# Input_v1_0.net
KiCad netlist of a schematic drawn in EAGLE
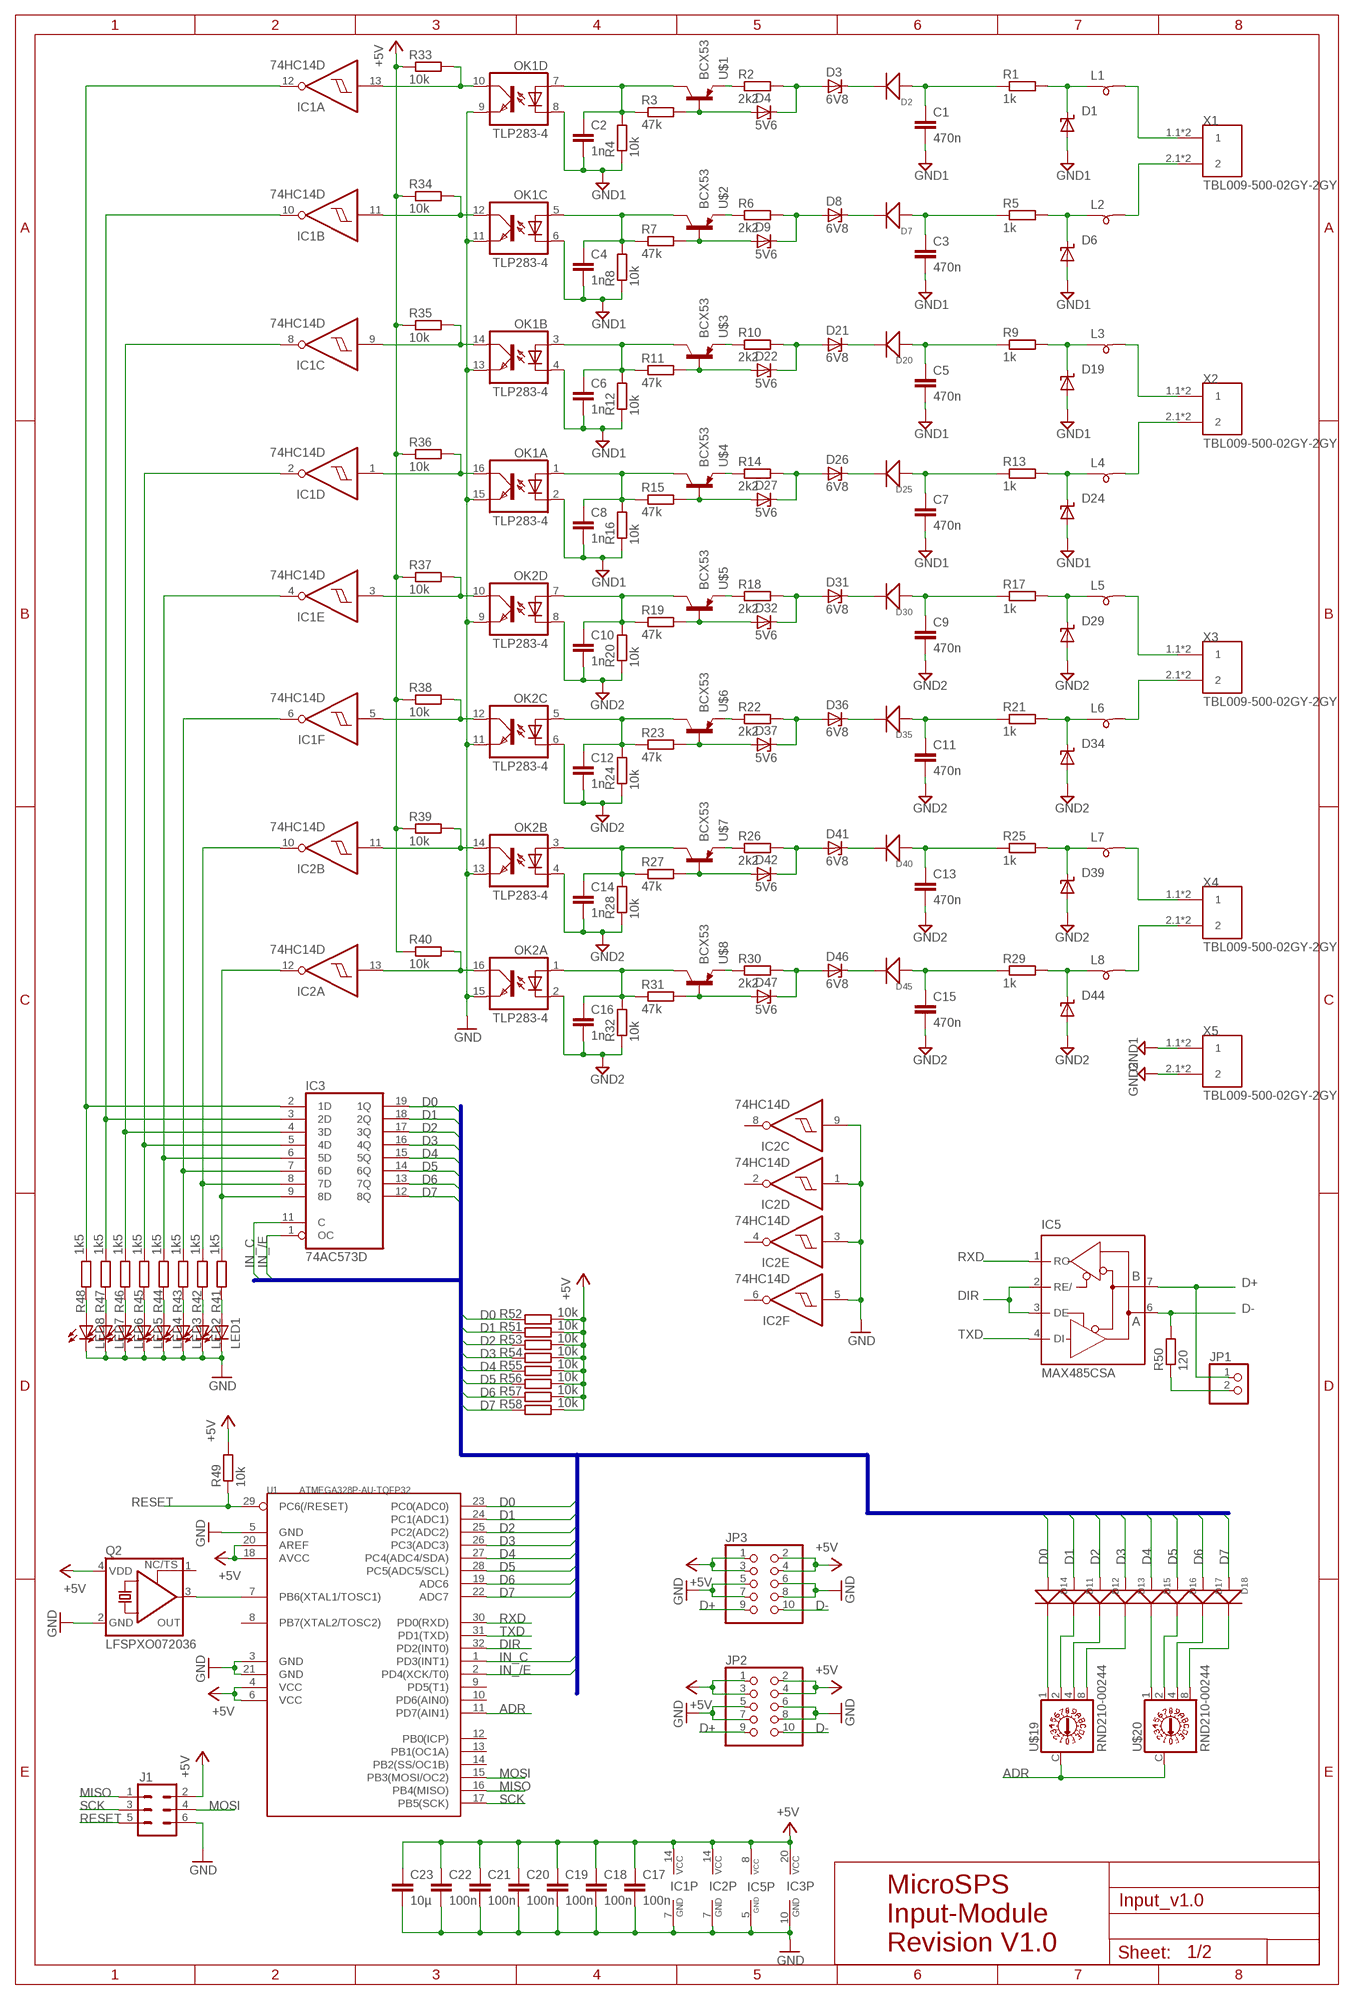
[diagram p0: schematic, sheet 1]

(export (version "E")
  (design (tool "Eeschema 10.0.6"))
  (components
    (comp (ref "C1")
      (value "470n")
      (footprint "eagle-import:C0805")
      (libsource (lib "eagle-import") (part "C-EUC0805"))
    )
    (comp (ref "C2")
      (value "1n")
      (footprint "eagle-import:C0805")
      (libsource (lib "eagle-import") (part "C-EUC0805"))
    )
    (comp (ref "C3")
      (value "470n")
      (footprint "eagle-import:C0805")
      (libsource (lib "eagle-import") (part "C-EUC0805"))
    )
    (comp (ref "C4")
      (value "1n")
      (footprint "eagle-import:C0805")
      (libsource (lib "eagle-import") (part "C-EUC0805"))
    )
    (comp (ref "C5")
      (value "470n")
      (footprint "eagle-import:C0805")
      (libsource (lib "eagle-import") (part "C-EUC0805"))
    )
    (comp (ref "C6")
      (value "1n")
      (footprint "eagle-import:C0805")
      (libsource (lib "eagle-import") (part "C-EUC0805"))
    )
    (comp (ref "C7")
      (value "470n")
      (footprint "eagle-import:C0805")
      (libsource (lib "eagle-import") (part "C-EUC0805"))
    )
    (comp (ref "C8")
      (value "1n")
      (footprint "eagle-import:C0805")
      (libsource (lib "eagle-import") (part "C-EUC0805"))
    )
    (comp (ref "C9")
      (value "470n")
      (footprint "eagle-import:C0805")
      (libsource (lib "eagle-import") (part "C-EUC0805"))
    )
    (comp (ref "C10")
      (value "1n")
      (footprint "eagle-import:C0805")
      (libsource (lib "eagle-import") (part "C-EUC0805"))
    )
    (comp (ref "C11")
      (value "470n")
      (footprint "eagle-import:C0805")
      (libsource (lib "eagle-import") (part "C-EUC0805"))
    )
    (comp (ref "C12")
      (value "1n")
      (footprint "eagle-import:C0805")
      (libsource (lib "eagle-import") (part "C-EUC0805"))
    )
    (comp (ref "C13")
      (value "470n")
      (footprint "eagle-import:C0805")
      (libsource (lib "eagle-import") (part "C-EUC0805"))
    )
    (comp (ref "C14")
      (value "1n")
      (footprint "eagle-import:C0805")
      (libsource (lib "eagle-import") (part "C-EUC0805"))
    )
    (comp (ref "C15")
      (value "470n")
      (footprint "eagle-import:C0805")
      (libsource (lib "eagle-import") (part "C-EUC0805"))
    )
    (comp (ref "C16")
      (value "1n")
      (footprint "eagle-import:C0805")
      (libsource (lib "eagle-import") (part "C-EUC0805"))
    )
    (comp (ref "C17")
      (value "100n")
      (footprint "eagle-import:C0805")
      (libsource (lib "eagle-import") (part "C-EUC0805"))
    )
    (comp (ref "C18")
      (value "100n")
      (footprint "eagle-import:C0805")
      (libsource (lib "eagle-import") (part "C-EUC0805"))
    )
    (comp (ref "C19")
      (value "100n")
      (footprint "eagle-import:C0805")
      (libsource (lib "eagle-import") (part "C-EUC0805"))
    )
    (comp (ref "C20")
      (value "100n")
      (footprint "eagle-import:C0805")
      (libsource (lib "eagle-import") (part "C-EUC0805"))
    )
    (comp (ref "C21")
      (value "100n")
      (footprint "eagle-import:C0805")
      (libsource (lib "eagle-import") (part "C-EUC0805"))
    )
    (comp (ref "C22")
      (value "100n")
      (footprint "eagle-import:C0805")
      (libsource (lib "eagle-import") (part "C-EUC0805"))
    )
    (comp (ref "C23")
      (value "10µ")
      (footprint "eagle-import:C0805")
      (libsource (lib "eagle-import") (part "C-EUC0805"))
    )
    (comp (ref "D1")
      (value "SUPPRESSOR-SMBJ")
      (footprint "eagle-import:SMBJ")
      (libsource (lib "eagle-import") (part "SUPPRESSOR-SMBJ"))
    )
    (comp (ref "D2")
      (value "DIODE'1N4148-SMD'")
      (footprint "eagle-import:LL-34")
      (libsource (lib "eagle-import") (part "DIODE'1N4148-SMD'"))
    )
    (comp (ref "D3")
      (value "6V8")
      (footprint "eagle-import:SOD80C")
      (libsource (lib "eagle-import") (part "ZENER-DIODESOD80C"))
    )
    (comp (ref "D4")
      (value "5V6")
      (footprint "eagle-import:SOD80C")
      (libsource (lib "eagle-import") (part "ZENER-DIODESOD80C"))
    )
    (comp (ref "D6")
      (value "SUPPRESSOR-SMBJ")
      (footprint "eagle-import:SMBJ")
      (libsource (lib "eagle-import") (part "SUPPRESSOR-SMBJ"))
    )
    (comp (ref "D7")
      (value "DIODE'1N4148-SMD'")
      (footprint "eagle-import:LL-34")
      (libsource (lib "eagle-import") (part "DIODE'1N4148-SMD'"))
    )
    (comp (ref "D8")
      (value "6V8")
      (footprint "eagle-import:SOD80C")
      (libsource (lib "eagle-import") (part "ZENER-DIODESOD80C"))
    )
    (comp (ref "D9")
      (value "5V6")
      (footprint "eagle-import:SOD80C")
      (libsource (lib "eagle-import") (part "ZENER-DIODESOD80C"))
    )
    (comp (ref "D11")
      (value "DIODE'1N4148-SMD'")
      (footprint "eagle-import:LL-34")
      (libsource (lib "eagle-import") (part "DIODE'1N4148-SMD'"))
    )
    (comp (ref "D12")
      (value "DIODE'1N4148-SMD'")
      (footprint "eagle-import:LL-34")
      (libsource (lib "eagle-import") (part "DIODE'1N4148-SMD'"))
    )
    (comp (ref "D13")
      (value "DIODE'1N4148-SMD'")
      (footprint "eagle-import:LL-34")
      (libsource (lib "eagle-import") (part "DIODE'1N4148-SMD'"))
    )
    (comp (ref "D14")
      (value "DIODE'1N4148-SMD'")
      (footprint "eagle-import:LL-34")
      (libsource (lib "eagle-import") (part "DIODE'1N4148-SMD'"))
    )
    (comp (ref "D15")
      (value "DIODE'1N4148-SMD'")
      (footprint "eagle-import:LL-34")
      (libsource (lib "eagle-import") (part "DIODE'1N4148-SMD'"))
    )
    (comp (ref "D16")
      (value "DIODE'1N4148-SMD'")
      (footprint "eagle-import:LL-34")
      (libsource (lib "eagle-import") (part "DIODE'1N4148-SMD'"))
    )
    (comp (ref "D17")
      (value "DIODE'1N4148-SMD'")
      (footprint "eagle-import:LL-34")
      (libsource (lib "eagle-import") (part "DIODE'1N4148-SMD'"))
    )
    (comp (ref "D18")
      (value "DIODE'1N4148-SMD'")
      (footprint "eagle-import:LL-34")
      (libsource (lib "eagle-import") (part "DIODE'1N4148-SMD'"))
    )
    (comp (ref "D19")
      (value "SUPPRESSOR-SMBJ")
      (footprint "eagle-import:SMBJ")
      (libsource (lib "eagle-import") (part "SUPPRESSOR-SMBJ"))
    )
    (comp (ref "D20")
      (value "DIODE'1N4148-SMD'")
      (footprint "eagle-import:LL-34")
      (libsource (lib "eagle-import") (part "DIODE'1N4148-SMD'"))
    )
    (comp (ref "D21")
      (value "6V8")
      (footprint "eagle-import:SOD80C")
      (libsource (lib "eagle-import") (part "ZENER-DIODESOD80C"))
    )
    (comp (ref "D22")
      (value "5V6")
      (footprint "eagle-import:SOD80C")
      (libsource (lib "eagle-import") (part "ZENER-DIODESOD80C"))
    )
    (comp (ref "D24")
      (value "SUPPRESSOR-SMBJ")
      (footprint "eagle-import:SMBJ")
      (libsource (lib "eagle-import") (part "SUPPRESSOR-SMBJ"))
    )
    (comp (ref "D25")
      (value "DIODE'1N4148-SMD'")
      (footprint "eagle-import:LL-34")
      (libsource (lib "eagle-import") (part "DIODE'1N4148-SMD'"))
    )
    (comp (ref "D26")
      (value "6V8")
      (footprint "eagle-import:SOD80C")
      (libsource (lib "eagle-import") (part "ZENER-DIODESOD80C"))
    )
    (comp (ref "D27")
      (value "5V6")
      (footprint "eagle-import:SOD80C")
      (libsource (lib "eagle-import") (part "ZENER-DIODESOD80C"))
    )
    (comp (ref "D29")
      (value "SUPPRESSOR-SMBJ")
      (footprint "eagle-import:SMBJ")
      (libsource (lib "eagle-import") (part "SUPPRESSOR-SMBJ"))
    )
    (comp (ref "D30")
      (value "DIODE'1N4148-SMD'")
      (footprint "eagle-import:LL-34")
      (libsource (lib "eagle-import") (part "DIODE'1N4148-SMD'"))
    )
    (comp (ref "D31")
      (value "6V8")
      (footprint "eagle-import:SOD80C")
      (libsource (lib "eagle-import") (part "ZENER-DIODESOD80C"))
    )
    (comp (ref "D32")
      (value "5V6")
      (footprint "eagle-import:SOD80C")
      (libsource (lib "eagle-import") (part "ZENER-DIODESOD80C"))
    )
    (comp (ref "D34")
      (value "SUPPRESSOR-SMBJ")
      (footprint "eagle-import:SMBJ")
      (libsource (lib "eagle-import") (part "SUPPRESSOR-SMBJ"))
    )
    (comp (ref "D35")
      (value "DIODE'1N4148-SMD'")
      (footprint "eagle-import:LL-34")
      (libsource (lib "eagle-import") (part "DIODE'1N4148-SMD'"))
    )
    (comp (ref "D36")
      (value "6V8")
      (footprint "eagle-import:SOD80C")
      (libsource (lib "eagle-import") (part "ZENER-DIODESOD80C"))
    )
    (comp (ref "D37")
      (value "5V6")
      (footprint "eagle-import:SOD80C")
      (libsource (lib "eagle-import") (part "ZENER-DIODESOD80C"))
    )
    (comp (ref "D39")
      (value "SUPPRESSOR-SMBJ")
      (footprint "eagle-import:SMBJ")
      (libsource (lib "eagle-import") (part "SUPPRESSOR-SMBJ"))
    )
    (comp (ref "D40")
      (value "DIODE'1N4148-SMD'")
      (footprint "eagle-import:LL-34")
      (libsource (lib "eagle-import") (part "DIODE'1N4148-SMD'"))
    )
    (comp (ref "D41")
      (value "6V8")
      (footprint "eagle-import:SOD80C")
      (libsource (lib "eagle-import") (part "ZENER-DIODESOD80C"))
    )
    (comp (ref "D42")
      (value "5V6")
      (footprint "eagle-import:SOD80C")
      (libsource (lib "eagle-import") (part "ZENER-DIODESOD80C"))
    )
    (comp (ref "D44")
      (value "SUPPRESSOR-SMBJ")
      (footprint "eagle-import:SMBJ")
      (libsource (lib "eagle-import") (part "SUPPRESSOR-SMBJ"))
    )
    (comp (ref "D45")
      (value "DIODE'1N4148-SMD'")
      (footprint "eagle-import:LL-34")
      (libsource (lib "eagle-import") (part "DIODE'1N4148-SMD'"))
    )
    (comp (ref "D46")
      (value "6V8")
      (footprint "eagle-import:SOD80C")
      (libsource (lib "eagle-import") (part "ZENER-DIODESOD80C"))
    )
    (comp (ref "D47")
      (value "5V6")
      (footprint "eagle-import:SOD80C")
      (libsource (lib "eagle-import") (part "ZENER-DIODESOD80C"))
    )
    (comp (ref "IC1")
      (value "74HC14D")
      (footprint "eagle-import:SO14")
      (libsource (lib "eagle-import") (part "7414DHC"))
    )
    (comp (ref "IC2")
      (value "74HC14D")
      (footprint "eagle-import:SO14")
      (libsource (lib "eagle-import") (part "7414DHC"))
    )
    (comp (ref "IC3")
      (value "74AC573D")
      (footprint "eagle-import:SO20W")
      (libsource (lib "eagle-import") (part "74573DAC"))
    )
    (comp (ref "IC5")
      (value "MAX485CSA")
      (footprint "eagle-import:SO08")
      (fields (field (name "MF") "MAXIM") (field (name "MPN") "MAX481CSA"))
      (libsource (lib "eagle-import") (part "MAX481CSA"))
    )
    (comp (ref "J1")
      (value "CONN_03X2FEMALE_SMD")
      (footprint "eagle-import:2X3_SMD")
      (libsource (lib "eagle-import") (part "CONN_03X2FEMALE_SMD"))
    )
    (comp (ref "JP1")
      (value "PINHD-1X2")
      (footprint "eagle-import:1X02")
      (libsource (lib "eagle-import") (part "PINHD-1X2"))
    )
    (comp (ref "JP2")
      (value "PINHD-2X5/90")
      (footprint "eagle-import:2X05_90")
      (libsource (lib "eagle-import") (part "PINHD-2X5/90"))
    )
    (comp (ref "JP3")
      (value "PINHD-2X5/90")
      (footprint "eagle-import:2X05_90")
      (libsource (lib "eagle-import") (part "PINHD-2X5/90"))
    )
    (comp (ref "L1")
      (value "SM-B5")
      (footprint "eagle-import:SM-B5")
      (libsource (lib "eagle-import") (part "SM-B5"))
    )
    (comp (ref "L2")
      (value "SM-B5")
      (footprint "eagle-import:SM-B5")
      (libsource (lib "eagle-import") (part "SM-B5"))
    )
    (comp (ref "L3")
      (value "SM-B5")
      (footprint "eagle-import:SM-B5")
      (libsource (lib "eagle-import") (part "SM-B5"))
    )
    (comp (ref "L4")
      (value "SM-B5")
      (footprint "eagle-import:SM-B5")
      (libsource (lib "eagle-import") (part "SM-B5"))
    )
    (comp (ref "L5")
      (value "SM-B5")
      (footprint "eagle-import:SM-B5")
      (libsource (lib "eagle-import") (part "SM-B5"))
    )
    (comp (ref "L6")
      (value "SM-B5")
      (footprint "eagle-import:SM-B5")
      (libsource (lib "eagle-import") (part "SM-B5"))
    )
    (comp (ref "L7")
      (value "SM-B5")
      (footprint "eagle-import:SM-B5")
      (libsource (lib "eagle-import") (part "SM-B5"))
    )
    (comp (ref "L8")
      (value "SM-B5")
      (footprint "eagle-import:SM-B5")
      (libsource (lib "eagle-import") (part "SM-B5"))
    )
    (comp (ref "LED1")
      (value "LED3MM")
      (footprint "eagle-import:LED3MM")
      (libsource (lib "eagle-import") (part "LED3MM"))
    )
    (comp (ref "LED2")
      (value "LED3MM")
      (footprint "eagle-import:LED3MM")
      (libsource (lib "eagle-import") (part "LED3MM"))
    )
    (comp (ref "LED3")
      (value "LED3MM")
      (footprint "eagle-import:LED3MM")
      (libsource (lib "eagle-import") (part "LED3MM"))
    )
    (comp (ref "LED4")
      (value "LED3MM")
      (footprint "eagle-import:LED3MM")
      (libsource (lib "eagle-import") (part "LED3MM"))
    )
    (comp (ref "LED5")
      (value "LED3MM")
      (footprint "eagle-import:LED3MM")
      (libsource (lib "eagle-import") (part "LED3MM"))
    )
    (comp (ref "LED6")
      (value "LED3MM")
      (footprint "eagle-import:LED3MM")
      (libsource (lib "eagle-import") (part "LED3MM"))
    )
    (comp (ref "LED7")
      (value "LED3MM")
      (footprint "eagle-import:LED3MM")
      (libsource (lib "eagle-import") (part "LED3MM"))
    )
    (comp (ref "LED8")
      (value "LED3MM")
      (footprint "eagle-import:LED3MM")
      (libsource (lib "eagle-import") (part "LED3MM"))
    )
    (comp (ref "OK1")
      (value "TLP283-4")
      (footprint "eagle-import:MINI-FLAT-16")
      (libsource (lib "eagle-import") (part "TLP283-4"))
    )
    (comp (ref "OK2")
      (value "TLP283-4")
      (footprint "eagle-import:MINI-FLAT-16")
      (libsource (lib "eagle-import") (part "TLP283-4"))
    )
    (comp (ref "Q2")
      (value "LFSPXO072036")
      (footprint "eagle-import:5.0X3.2_KXO-56")
      (libsource (lib "eagle-import") (part "KXO-PXO/XO-56-56"))
    )
    (comp (ref "R1")
      (value "1k")
      (footprint "eagle-import:R0805")
      (libsource (lib "eagle-import") (part "R-EU_R0805"))
    )
    (comp (ref "R2")
      (value "2k2")
      (footprint "eagle-import:R0805")
      (libsource (lib "eagle-import") (part "R-EU_R0805"))
    )
    (comp (ref "R3")
      (value "47k")
      (footprint "eagle-import:R0805")
      (libsource (lib "eagle-import") (part "R-EU_R0805"))
    )
    (comp (ref "R4")
      (value "10k")
      (footprint "eagle-import:R0805")
      (libsource (lib "eagle-import") (part "R-EU_R0805"))
    )
    (comp (ref "R5")
      (value "1k")
      (footprint "eagle-import:R0805")
      (libsource (lib "eagle-import") (part "R-EU_R0805"))
    )
    (comp (ref "R6")
      (value "2k2")
      (footprint "eagle-import:R0805")
      (libsource (lib "eagle-import") (part "R-EU_R0805"))
    )
    (comp (ref "R7")
      (value "47k")
      (footprint "eagle-import:R0805")
      (libsource (lib "eagle-import") (part "R-EU_R0805"))
    )
    (comp (ref "R8")
      (value "10k")
      (footprint "eagle-import:R0805")
      (libsource (lib "eagle-import") (part "R-EU_R0805"))
    )
    (comp (ref "R9")
      (value "1k")
      (footprint "eagle-import:R0805")
      (libsource (lib "eagle-import") (part "R-EU_R0805"))
    )
    (comp (ref "R10")
      (value "2k2")
      (footprint "eagle-import:R0805")
      (libsource (lib "eagle-import") (part "R-EU_R0805"))
    )
    (comp (ref "R11")
      (value "47k")
      (footprint "eagle-import:R0805")
      (libsource (lib "eagle-import") (part "R-EU_R0805"))
    )
    (comp (ref "R12")
      (value "10k")
      (footprint "eagle-import:R0805")
      (libsource (lib "eagle-import") (part "R-EU_R0805"))
    )
    (comp (ref "R13")
      (value "1k")
      (footprint "eagle-import:R0805")
      (libsource (lib "eagle-import") (part "R-EU_R0805"))
    )
    (comp (ref "R14")
      (value "2k2")
      (footprint "eagle-import:R0805")
      (libsource (lib "eagle-import") (part "R-EU_R0805"))
    )
    (comp (ref "R15")
      (value "47k")
      (footprint "eagle-import:R0805")
      (libsource (lib "eagle-import") (part "R-EU_R0805"))
    )
    (comp (ref "R16")
      (value "10k")
      (footprint "eagle-import:R0805")
      (libsource (lib "eagle-import") (part "R-EU_R0805"))
    )
    (comp (ref "R17")
      (value "1k")
      (footprint "eagle-import:R0805")
      (libsource (lib "eagle-import") (part "R-EU_R0805"))
    )
    (comp (ref "R18")
      (value "2k2")
      (footprint "eagle-import:R0805")
      (libsource (lib "eagle-import") (part "R-EU_R0805"))
    )
    (comp (ref "R19")
      (value "47k")
      (footprint "eagle-import:R0805")
      (libsource (lib "eagle-import") (part "R-EU_R0805"))
    )
    (comp (ref "R20")
      (value "10k")
      (footprint "eagle-import:R0805")
      (libsource (lib "eagle-import") (part "R-EU_R0805"))
    )
    (comp (ref "R21")
      (value "1k")
      (footprint "eagle-import:R0805")
      (libsource (lib "eagle-import") (part "R-EU_R0805"))
    )
    (comp (ref "R22")
      (value "2k2")
      (footprint "eagle-import:R0805")
      (libsource (lib "eagle-import") (part "R-EU_R0805"))
    )
    (comp (ref "R23")
      (value "47k")
      (footprint "eagle-import:R0805")
      (libsource (lib "eagle-import") (part "R-EU_R0805"))
    )
    (comp (ref "R24")
      (value "10k")
      (footprint "eagle-import:R0805")
      (libsource (lib "eagle-import") (part "R-EU_R0805"))
    )
    (comp (ref "R25")
      (value "1k")
      (footprint "eagle-import:R0805")
      (libsource (lib "eagle-import") (part "R-EU_R0805"))
    )
    (comp (ref "R26")
      (value "2k2")
      (footprint "eagle-import:R0805")
      (libsource (lib "eagle-import") (part "R-EU_R0805"))
    )
    (comp (ref "R27")
      (value "47k")
      (footprint "eagle-import:R0805")
      (libsource (lib "eagle-import") (part "R-EU_R0805"))
    )
    (comp (ref "R28")
      (value "10k")
      (footprint "eagle-import:R0805")
      (libsource (lib "eagle-import") (part "R-EU_R0805"))
    )
    (comp (ref "R29")
      (value "1k")
      (footprint "eagle-import:R0805")
      (libsource (lib "eagle-import") (part "R-EU_R0805"))
    )
    (comp (ref "R30")
      (value "2k2")
      (footprint "eagle-import:R0805")
      (libsource (lib "eagle-import") (part "R-EU_R0805"))
    )
    (comp (ref "R31")
      (value "47k")
      (footprint "eagle-import:R0805")
      (libsource (lib "eagle-import") (part "R-EU_R0805"))
    )
    (comp (ref "R32")
      (value "10k")
      (footprint "eagle-import:R0805")
      (libsource (lib "eagle-import") (part "R-EU_R0805"))
    )
    (comp (ref "R33")
      (value "10k")
      (footprint "eagle-import:R0805")
      (libsource (lib "eagle-import") (part "R-EU_R0805"))
    )
    (comp (ref "R34")
      (value "10k")
      (footprint "eagle-import:R0805")
      (libsource (lib "eagle-import") (part "R-EU_R0805"))
    )
    (comp (ref "R35")
      (value "10k")
      (footprint "eagle-import:R0805")
      (libsource (lib "eagle-import") (part "R-EU_R0805"))
    )
    (comp (ref "R36")
      (value "10k")
      (footprint "eagle-import:R0805")
      (libsource (lib "eagle-import") (part "R-EU_R0805"))
    )
    (comp (ref "R37")
      (value "10k")
      (footprint "eagle-import:R0805")
      (libsource (lib "eagle-import") (part "R-EU_R0805"))
    )
    (comp (ref "R38")
      (value "10k")
      (footprint "eagle-import:R0805")
      (libsource (lib "eagle-import") (part "R-EU_R0805"))
    )
    (comp (ref "R39")
      (value "10k")
      (footprint "eagle-import:R0805")
      (libsource (lib "eagle-import") (part "R-EU_R0805"))
    )
    (comp (ref "R40")
      (value "10k")
      (footprint "eagle-import:R0805")
      (libsource (lib "eagle-import") (part "R-EU_R0805"))
    )
    (comp (ref "R41")
      (value "1k5")
      (footprint "eagle-import:R0805")
      (libsource (lib "eagle-import") (part "R-EU_R0805"))
    )
    (comp (ref "R42")
      (value "1k5")
      (footprint "eagle-import:R0805")
      (libsource (lib "eagle-import") (part "R-EU_R0805"))
    )
    (comp (ref "R43")
      (value "1k5")
      (footprint "eagle-import:R0805")
      (libsource (lib "eagle-import") (part "R-EU_R0805"))
    )
    (comp (ref "R44")
      (value "1k5")
      (footprint "eagle-import:R0805")
      (libsource (lib "eagle-import") (part "R-EU_R0805"))
    )
    (comp (ref "R45")
      (value "1k5")
      (footprint "eagle-import:R0805")
      (libsource (lib "eagle-import") (part "R-EU_R0805"))
    )
    (comp (ref "R46")
      (value "1k5")
      (footprint "eagle-import:R0805")
      (libsource (lib "eagle-import") (part "R-EU_R0805"))
    )
    (comp (ref "R47")
      (value "1k5")
      (footprint "eagle-import:R0805")
      (libsource (lib "eagle-import") (part "R-EU_R0805"))
    )
    (comp (ref "R48")
      (value "1k5")
      (footprint "eagle-import:R0805")
      (libsource (lib "eagle-import") (part "R-EU_R0805"))
    )
    (comp (ref "R49")
      (value "10k")
      (footprint "eagle-import:R0805")
      (libsource (lib "eagle-import") (part "R-EU_R0805"))
    )
    (comp (ref "R50")
      (value "120")
      (footprint "eagle-import:R0805")
      (libsource (lib "eagle-import") (part "R-EU_R0805"))
    )
    (comp (ref "R51")
      (value "10k")
      (footprint "eagle-import:R0805")
      (libsource (lib "eagle-import") (part "R-EU_R0805"))
    )
    (comp (ref "R52")
      (value "10k")
      (footprint "eagle-import:R0805")
      (libsource (lib "eagle-import") (part "R-EU_R0805"))
    )
    (comp (ref "R53")
      (value "10k")
      (footprint "eagle-import:R0805")
      (libsource (lib "eagle-import") (part "R-EU_R0805"))
    )
    (comp (ref "R54")
      (value "10k")
      (footprint "eagle-import:R0805")
      (libsource (lib "eagle-import") (part "R-EU_R0805"))
    )
    (comp (ref "R55")
      (value "10k")
      (footprint "eagle-import:R0805")
      (libsource (lib "eagle-import") (part "R-EU_R0805"))
    )
    (comp (ref "R56")
      (value "10k")
      (footprint "eagle-import:R0805")
      (libsource (lib "eagle-import") (part "R-EU_R0805"))
    )
    (comp (ref "R57")
      (value "10k")
      (footprint "eagle-import:R0805")
      (libsource (lib "eagle-import") (part "R-EU_R0805"))
    )
    (comp (ref "R58")
      (value "10k")
      (footprint "eagle-import:R0805")
      (libsource (lib "eagle-import") (part "R-EU_R0805"))
    )
    (comp (ref "U$1")
      (value "BCX53")
      (footprint "eagle-import:SOT89")
      (libsource (lib "eagle-import") (part "BCX53"))
    )
    (comp (ref "U$2")
      (value "BCX53")
      (footprint "eagle-import:SOT89")
      (libsource (lib "eagle-import") (part "BCX53"))
    )
    (comp (ref "U$3")
      (value "BCX53")
      (footprint "eagle-import:SOT89")
      (libsource (lib "eagle-import") (part "BCX53"))
    )
    (comp (ref "U$4")
      (value "BCX53")
      (footprint "eagle-import:SOT89")
      (libsource (lib "eagle-import") (part "BCX53"))
    )
    (comp (ref "U$5")
      (value "BCX53")
      (footprint "eagle-import:SOT89")
      (libsource (lib "eagle-import") (part "BCX53"))
    )
    (comp (ref "U$6")
      (value "BCX53")
      (footprint "eagle-import:SOT89")
      (libsource (lib "eagle-import") (part "BCX53"))
    )
    (comp (ref "U$7")
      (value "BCX53")
      (footprint "eagle-import:SOT89")
      (libsource (lib "eagle-import") (part "BCX53"))
    )
    (comp (ref "U$8")
      (value "BCX53")
      (footprint "eagle-import:SOT89")
      (libsource (lib "eagle-import") (part "BCX53"))
    )
    (comp (ref "U$19")
      (value "RND210-00244")
      (footprint "eagle-import:RND210-00244")
      (libsource (lib "eagle-import") (part "RND210-00244"))
    )
    (comp (ref "U$20")
      (value "RND210-00244")
      (footprint "eagle-import:RND210-00244")
      (libsource (lib "eagle-import") (part "RND210-00244"))
    )
    (comp (ref "U1")
      (value "ATMEGA328P-AU-TQFP32")
      (footprint "eagle-import:TQFP32-0.8-7X7MM")
      (fields (field (name "MPN") "ATMEGA328P-AU"))
      (libsource (lib "eagle-import") (part "MCU-ATMEGA328P-AU(TQFP32)"))
    )
    (comp (ref "X1")
      (value "TBL009-500-02GY-2GY")
      (footprint "eagle-import:TBL009-500-02GY-2GY")
      (libsource (lib "eagle-import") (part "TBL009-500-02GY-2GY"))
    )
    (comp (ref "X2")
      (value "TBL009-500-02GY-2GY")
      (footprint "eagle-import:TBL009-500-02GY-2GY")
      (libsource (lib "eagle-import") (part "TBL009-500-02GY-2GY"))
    )
    (comp (ref "X3")
      (value "TBL009-500-02GY-2GY")
      (footprint "eagle-import:TBL009-500-02GY-2GY")
      (libsource (lib "eagle-import") (part "TBL009-500-02GY-2GY"))
    )
    (comp (ref "X4")
      (value "TBL009-500-02GY-2GY")
      (footprint "eagle-import:TBL009-500-02GY-2GY")
      (libsource (lib "eagle-import") (part "TBL009-500-02GY-2GY"))
    )
    (comp (ref "X5")
      (value "TBL009-500-02GY-2GY")
      (footprint "eagle-import:TBL009-500-02GY-2GY")
      (libsource (lib "eagle-import") (part "TBL009-500-02GY-2GY"))
    )
  )
  (nets
    (net (code "1") (name "+5V") (class "Default")
      (node (ref "C17") (pin "1") (pinfunction "1_1") (pintype "passive"))
      (node (ref "C18") (pin "1") (pinfunction "1_1") (pintype "passive"))
      (node (ref "C19") (pin "1") (pinfunction "1_1") (pintype "passive"))
      (node (ref "C20") (pin "1") (pinfunction "1_1") (pintype "passive"))
      (node (ref "C21") (pin "1") (pinfunction "1_1") (pintype "passive"))
      (node (ref "C22") (pin "1") (pinfunction "1_1") (pintype "passive"))
      (node (ref "C23") (pin "1") (pinfunction "1_1") (pintype "passive"))
      (node (ref "IC1") (pin "14") (pinfunction "VCC_14") (pintype "power_in"))
      (node (ref "IC2") (pin "14") (pinfunction "VCC_14") (pintype "power_in"))
      (node (ref "IC3") (pin "20") (pinfunction "VCC_20") (pintype "power_in"))
      (node (ref "IC5") (pin "8") (pinfunction "VCC_8") (pintype "power_in"))
      (node (ref "J1") (pin "2") (pinfunction "2_2") (pintype "bidirectional"))
      (node (ref "JP2") (pin "1") (pinfunction "1_1") (pintype "passive"))
      (node (ref "JP2") (pin "2") (pinfunction "2_2") (pintype "passive"))
      (node (ref "JP2") (pin "3") (pinfunction "3_3") (pintype "passive"))
      (node (ref "JP2") (pin "4") (pinfunction "4_4") (pintype "passive"))
      (node (ref "JP3") (pin "1") (pinfunction "1_1") (pintype "passive"))
      (node (ref "JP3") (pin "2") (pinfunction "2_2") (pintype "passive"))
      (node (ref "JP3") (pin "3") (pinfunction "3_3") (pintype "passive"))
      (node (ref "JP3") (pin "4") (pinfunction "4_4") (pintype "passive"))
      (node (ref "Q2") (pin "4") (pinfunction "VDD_4") (pintype "power_in"))
      (node (ref "R33") (pin "1") (pinfunction "1_1") (pintype "passive"))
      (node (ref "R34") (pin "1") (pinfunction "1_1") (pintype "passive"))
      (node (ref "R35") (pin "1") (pinfunction "1_1") (pintype "passive"))
      (node (ref "R36") (pin "1") (pinfunction "1_1") (pintype "passive"))
      (node (ref "R37") (pin "1") (pinfunction "1_1") (pintype "passive"))
      (node (ref "R38") (pin "1") (pinfunction "1_1") (pintype "passive"))
      (node (ref "R39") (pin "1") (pinfunction "1_1") (pintype "passive"))
      (node (ref "R40") (pin "1") (pinfunction "1_1") (pintype "passive"))
      (node (ref "R49") (pin "2") (pinfunction "2_2") (pintype "passive"))
      (node (ref "R51") (pin "2") (pinfunction "2_2") (pintype "passive"))
      (node (ref "R52") (pin "2") (pinfunction "2_2") (pintype "passive"))
      (node (ref "R53") (pin "2") (pinfunction "2_2") (pintype "passive"))
      (node (ref "R54") (pin "2") (pinfunction "2_2") (pintype "passive"))
      (node (ref "R55") (pin "2") (pinfunction "2_2") (pintype "passive"))
      (node (ref "R56") (pin "2") (pinfunction "2_2") (pintype "passive"))
      (node (ref "R57") (pin "2") (pinfunction "2_2") (pintype "passive"))
      (node (ref "R58") (pin "2") (pinfunction "2_2") (pintype "passive"))
      (node (ref "U1") (pin "18") (pinfunction "AVCC_18") (pintype "bidirectional"))
      (node (ref "U1") (pin "20") (pinfunction "AREF_20") (pintype "bidirectional"))
      (node (ref "U1") (pin "4") (pinfunction "VCC_4") (pintype "bidirectional"))
      (node (ref "U1") (pin "6") (pinfunction "VCC_6") (pintype "bidirectional"))
    )
    (net (code "2") (name "ADR") (class "Default")
      (node (ref "U$19") (pin "C") (pinfunction "C_C") (pintype "passive"))
      (node (ref "U$20") (pin "C") (pinfunction "C_C") (pintype "passive"))
      (node (ref "U1") (pin "11") (pinfunction "PD7(AIN1)_11") (pintype "bidirectional"))
    )
    (net (code "3") (name "D+") (class "Default")
      (node (ref "IC5") (pin "7") (pinfunction "B_7") (pintype "passive"))
      (node (ref "JP1") (pin "1") (pinfunction "1_1") (pintype "passive"))
      (node (ref "JP2") (pin "9") (pinfunction "9_9") (pintype "passive"))
      (node (ref "JP3") (pin "9") (pinfunction "9_9") (pintype "passive"))
    )
    (net (code "4") (name "D-") (class "Default")
      (node (ref "IC5") (pin "6") (pinfunction "A_6") (pintype "passive"))
      (node (ref "JP2") (pin "10") (pinfunction "10_10") (pintype "passive"))
      (node (ref "JP3") (pin "10") (pinfunction "10_10") (pintype "passive"))
      (node (ref "R50") (pin "2") (pinfunction "2_2") (pintype "passive"))
    )
    (net (code "5") (name "D0") (class "Default")
      (node (ref "D14") (pin "A") (pinfunction "+_A") (pintype "passive"))
      (node (ref "IC3") (pin "19") (pinfunction "1Q_19") (pintype "tri_state"))
      (node (ref "R52") (pin "1") (pinfunction "1_1") (pintype "passive"))
      (node (ref "U1") (pin "23") (pinfunction "PC0(ADC0)_23") (pintype "bidirectional"))
    )
    (net (code "6") (name "D1") (class "Default")
      (node (ref "D11") (pin "A") (pinfunction "+_A") (pintype "passive"))
      (node (ref "IC3") (pin "18") (pinfunction "2Q_18") (pintype "tri_state"))
      (node (ref "R51") (pin "1") (pinfunction "1_1") (pintype "passive"))
      (node (ref "U1") (pin "24") (pinfunction "PC1(ADC1)_24") (pintype "bidirectional"))
    )
    (net (code "7") (name "D2") (class "Default")
      (node (ref "D12") (pin "A") (pinfunction "+_A") (pintype "passive"))
      (node (ref "IC3") (pin "17") (pinfunction "3Q_17") (pintype "tri_state"))
      (node (ref "R53") (pin "1") (pinfunction "1_1") (pintype "passive"))
      (node (ref "U1") (pin "25") (pinfunction "PC2(ADC2)_25") (pintype "bidirectional"))
    )
    (net (code "8") (name "D3") (class "Default")
      (node (ref "D13") (pin "A") (pinfunction "+_A") (pintype "passive"))
      (node (ref "IC3") (pin "16") (pinfunction "4Q_16") (pintype "tri_state"))
      (node (ref "R54") (pin "1") (pinfunction "1_1") (pintype "passive"))
      (node (ref "U1") (pin "26") (pinfunction "PC3(ADC3)_26") (pintype "bidirectional"))
    )
    (net (code "9") (name "D4") (class "Default")
      (node (ref "D15") (pin "A") (pinfunction "+_A") (pintype "passive"))
      (node (ref "IC3") (pin "15") (pinfunction "5Q_15") (pintype "tri_state"))
      (node (ref "R55") (pin "1") (pinfunction "1_1") (pintype "passive"))
      (node (ref "U1") (pin "27") (pinfunction "PC4(ADC4/SDA)_27") (pintype "bidirectional"))
    )
    (net (code "10") (name "D5") (class "Default")
      (node (ref "D16") (pin "A") (pinfunction "+_A") (pintype "passive"))
      (node (ref "IC3") (pin "14") (pinfunction "6Q_14") (pintype "tri_state"))
      (node (ref "R56") (pin "1") (pinfunction "1_1") (pintype "passive"))
      (node (ref "U1") (pin "28") (pinfunction "PC5(ADC5/SCL)_28") (pintype "bidirectional"))
    )
    (net (code "11") (name "D6") (class "Default")
      (node (ref "D17") (pin "A") (pinfunction "+_A") (pintype "passive"))
      (node (ref "IC3") (pin "13") (pinfunction "7Q_13") (pintype "tri_state"))
      (node (ref "R57") (pin "1") (pinfunction "1_1") (pintype "passive"))
      (node (ref "U1") (pin "19") (pinfunction "ADC6_19") (pintype "bidirectional"))
    )
    (net (code "12") (name "D7") (class "Default")
      (node (ref "D18") (pin "A") (pinfunction "+_A") (pintype "passive"))
      (node (ref "IC3") (pin "12") (pinfunction "8Q_12") (pintype "tri_state"))
      (node (ref "R58") (pin "1") (pinfunction "1_1") (pintype "passive"))
      (node (ref "U1") (pin "22") (pinfunction "ADC7_22") (pintype "bidirectional"))
    )
    (net (code "13") (name "DIR") (class "Default")
      (node (ref "IC5") (pin "2") (pinfunction "RE/_2") (pintype "input"))
      (node (ref "IC5") (pin "3") (pinfunction "DE_3") (pintype "input"))
      (node (ref "U1") (pin "32") (pinfunction "PD2(INT0)_32") (pintype "bidirectional"))
    )
    (net (code "14") (name "GND") (class "Default")
      (node (ref "C17") (pin "2") (pinfunction "2_2") (pintype "passive"))
      (node (ref "C18") (pin "2") (pinfunction "2_2") (pintype "passive"))
      (node (ref "C19") (pin "2") (pinfunction "2_2") (pintype "passive"))
      (node (ref "C20") (pin "2") (pinfunction "2_2") (pintype "passive"))
      (node (ref "C21") (pin "2") (pinfunction "2_2") (pintype "passive"))
      (node (ref "C22") (pin "2") (pinfunction "2_2") (pintype "passive"))
      (node (ref "C23") (pin "2") (pinfunction "2_2") (pintype "passive"))
      (node (ref "IC1") (pin "7") (pinfunction "GND_7") (pintype "power_in"))
      (node (ref "IC2") (pin "1") (pinfunction "I_1") (pintype "input"))
      (node (ref "IC2") (pin "3") (pinfunction "I_3") (pintype "input"))
      (node (ref "IC2") (pin "5") (pinfunction "I_5") (pintype "input"))
      (node (ref "IC2") (pin "7") (pinfunction "GND_7") (pintype "power_in"))
      (node (ref "IC2") (pin "9") (pinfunction "I_9") (pintype "input"))
      (node (ref "IC3") (pin "10") (pinfunction "GND_10") (pintype "power_in"))
      (node (ref "IC5") (pin "5") (pinfunction "GND_5") (pintype "power_in"))
      (node (ref "J1") (pin "6") (pinfunction "6_6") (pintype "bidirectional"))
      (node (ref "JP2") (pin "5") (pinfunction "5_5") (pintype "passive"))
      (node (ref "JP2") (pin "6") (pinfunction "6_6") (pintype "passive"))
      (node (ref "JP2") (pin "7") (pinfunction "7_7") (pintype "passive"))
      (node (ref "JP2") (pin "8") (pinfunction "8_8") (pintype "passive"))
      (node (ref "JP3") (pin "5") (pinfunction "5_5") (pintype "passive"))
      (node (ref "JP3") (pin "6") (pinfunction "6_6") (pintype "passive"))
      (node (ref "JP3") (pin "7") (pinfunction "7_7") (pintype "passive"))
      (node (ref "JP3") (pin "8") (pinfunction "8_8") (pintype "passive"))
      (node (ref "LED1") (pin "K") (pinfunction "C_K") (pintype "passive"))
      (node (ref "LED2") (pin "K") (pinfunction "C_K") (pintype "passive"))
      (node (ref "LED3") (pin "K") (pinfunction "C_K") (pintype "passive"))
      (node (ref "LED4") (pin "K") (pinfunction "C_K") (pintype "passive"))
      (node (ref "LED5") (pin "K") (pinfunction "C_K") (pintype "passive"))
      (node (ref "LED6") (pin "K") (pinfunction "C_K") (pintype "passive"))
      (node (ref "LED7") (pin "K") (pinfunction "C_K") (pintype "passive"))
      (node (ref "LED8") (pin "K") (pinfunction "C_K") (pintype "passive"))
      (node (ref "OK1") (pin "11") (pinfunction "EMIT_11") (pintype "passive"))
      (node (ref "OK1") (pin "13") (pinfunction "EMIT_13") (pintype "passive"))
      (node (ref "OK1") (pin "15") (pinfunction "EMIT_15") (pintype "passive"))
      (node (ref "OK1") (pin "9") (pinfunction "EMIT_9") (pintype "passive"))
      (node (ref "OK2") (pin "11") (pinfunction "EMIT_11") (pintype "passive"))
      (node (ref "OK2") (pin "13") (pinfunction "EMIT_13") (pintype "passive"))
      (node (ref "OK2") (pin "15") (pinfunction "EMIT_15") (pintype "passive"))
      (node (ref "OK2") (pin "9") (pinfunction "EMIT_9") (pintype "passive"))
      (node (ref "Q2") (pin "2") (pinfunction "GND_2") (pintype "power_in"))
      (node (ref "U1") (pin "21") (pinfunction "GND_21") (pintype "bidirectional"))
      (node (ref "U1") (pin "3") (pinfunction "GND_3") (pintype "bidirectional"))
      (node (ref "U1") (pin "5") (pinfunction "GND_5") (pintype "bidirectional"))
    )
    (net (code "15") (name "GND1") (class "Default")
      (node (ref "C1") (pin "2") (pinfunction "2_2") (pintype "passive"))
      (node (ref "C2") (pin "2") (pinfunction "2_2") (pintype "passive"))
      (node (ref "C3") (pin "2") (pinfunction "2_2") (pintype "passive"))
      (node (ref "C4") (pin "2") (pinfunction "2_2") (pintype "passive"))
      (node (ref "C5") (pin "2") (pinfunction "2_2") (pintype "passive"))
      (node (ref "C6") (pin "2") (pinfunction "2_2") (pintype "passive"))
      (node (ref "C7") (pin "2") (pinfunction "2_2") (pintype "passive"))
      (node (ref "C8") (pin "2") (pinfunction "2_2") (pintype "passive"))
      (node (ref "D1") (pin "A") (pinfunction "A_A") (pintype "passive"))
      (node (ref "D19") (pin "A") (pinfunction "A_A") (pintype "passive"))
      (node (ref "D24") (pin "A") (pinfunction "A_A") (pintype "passive"))
      (node (ref "D6") (pin "A") (pinfunction "A_A") (pintype "passive"))
      (node (ref "OK1") (pin "2") (pinfunction "C_2") (pintype "passive"))
      (node (ref "OK1") (pin "4") (pinfunction "C_4") (pintype "passive"))
      (node (ref "OK1") (pin "6") (pinfunction "C_6") (pintype "passive"))
      (node (ref "OK1") (pin "8") (pinfunction "C_8") (pintype "passive"))
      (node (ref "R12") (pin "1") (pinfunction "1_1") (pintype "passive"))
      (node (ref "R16") (pin "1") (pinfunction "1_1") (pintype "passive"))
      (node (ref "R4") (pin "1") (pinfunction "1_1") (pintype "passive"))
      (node (ref "R8") (pin "1") (pinfunction "1_1") (pintype "passive"))
      (node (ref "X5") (pin "1.1") (pinfunction "1_1.1") (pintype "bidirectional"))
      (node (ref "X5") (pin "1.2") (pinfunction "1_1.2") (pintype "bidirectional"))
    )
    (net (code "16") (name "GND2") (class "Default")
      (node (ref "C10") (pin "2") (pinfunction "2_2") (pintype "passive"))
      (node (ref "C11") (pin "2") (pinfunction "2_2") (pintype "passive"))
      (node (ref "C12") (pin "2") (pinfunction "2_2") (pintype "passive"))
      (node (ref "C13") (pin "2") (pinfunction "2_2") (pintype "passive"))
      (node (ref "C14") (pin "2") (pinfunction "2_2") (pintype "passive"))
      (node (ref "C15") (pin "2") (pinfunction "2_2") (pintype "passive"))
      (node (ref "C16") (pin "2") (pinfunction "2_2") (pintype "passive"))
      (node (ref "C9") (pin "2") (pinfunction "2_2") (pintype "passive"))
      (node (ref "D29") (pin "A") (pinfunction "A_A") (pintype "passive"))
      (node (ref "D34") (pin "A") (pinfunction "A_A") (pintype "passive"))
      (node (ref "D39") (pin "A") (pinfunction "A_A") (pintype "passive"))
      (node (ref "D44") (pin "A") (pinfunction "A_A") (pintype "passive"))
      (node (ref "OK2") (pin "2") (pinfunction "C_2") (pintype "passive"))
      (node (ref "OK2") (pin "4") (pinfunction "C_4") (pintype "passive"))
      (node (ref "OK2") (pin "6") (pinfunction "C_6") (pintype "passive"))
      (node (ref "OK2") (pin "8") (pinfunction "C_8") (pintype "passive"))
      (node (ref "R20") (pin "1") (pinfunction "1_1") (pintype "passive"))
      (node (ref "R24") (pin "1") (pinfunction "1_1") (pintype "passive"))
      (node (ref "R28") (pin "1") (pinfunction "1_1") (pintype "passive"))
      (node (ref "R32") (pin "1") (pinfunction "1_1") (pintype "passive"))
      (node (ref "X5") (pin "2.1") (pinfunction "2_2.1") (pintype "bidirectional"))
      (node (ref "X5") (pin "2.2") (pinfunction "2_2.2") (pintype "bidirectional"))
    )
    (net (code "17") (name "IN_C") (class "Default")
      (node (ref "IC3") (pin "11") (pinfunction "C_11") (pintype "input"))
      (node (ref "U1") (pin "1") (pinfunction "PD3(INT1)_1") (pintype "bidirectional"))
    )
    (net (code "18") (name "IN_{slash}E") (class "Default")
      (node (ref "IC3") (pin "1") (pinfunction "OC_1") (pintype "input"))
      (node (ref "U1") (pin "2") (pinfunction "PD4(XCK/T0)_2") (pintype "bidirectional"))
    )
    (net (code "19") (name "MISO") (class "Default")
      (node (ref "J1") (pin "1") (pinfunction "1_1") (pintype "bidirectional"))
      (node (ref "U1") (pin "16") (pinfunction "PB4(MISO)_16") (pintype "bidirectional"))
    )
    (net (code "20") (name "MOSI") (class "Default")
      (node (ref "J1") (pin "4") (pinfunction "4_4") (pintype "bidirectional"))
      (node (ref "U1") (pin "15") (pinfunction "PB3(MOSI/OC2)_15") (pintype "bidirectional"))
    )
    (net (code "21") (name "Net-(D1-PadC)") (class "Default")
      (node (ref "D1") (pin "C") (pinfunction "C_C") (pintype "passive"))
      (node (ref "L1") (pin "1") (pinfunction "1_1") (pintype "passive"))
      (node (ref "R1") (pin "2") (pinfunction "2_2") (pintype "passive"))
    )
    (net (code "22") (name "Net-(D2-+)") (class "Default")
      (node (ref "C1") (pin "1") (pinfunction "1_1") (pintype "passive"))
      (node (ref "D2") (pin "A") (pinfunction "+_A") (pintype "passive"))
      (node (ref "R1") (pin "1") (pinfunction "1_1") (pintype "passive"))
    )
    (net (code "23") (name "Net-(D2--)") (class "Default")
      (node (ref "D2") (pin "C") (pinfunction "-_C") (pintype "passive"))
      (node (ref "D3") (pin "C") (pinfunction "C_C") (pintype "passive"))
    )
    (net (code "24") (name "Net-(D3-PadA)") (class "Default")
      (node (ref "D3") (pin "A") (pinfunction "A_A") (pintype "passive"))
      (node (ref "D4") (pin "C") (pinfunction "C_C") (pintype "passive"))
      (node (ref "R2") (pin "2") (pinfunction "2_2") (pintype "passive"))
    )
    (net (code "25") (name "Net-(D6-PadC)") (class "Default")
      (node (ref "D6") (pin "C") (pinfunction "C_C") (pintype "passive"))
      (node (ref "L2") (pin "1") (pinfunction "1_1") (pintype "passive"))
      (node (ref "R5") (pin "2") (pinfunction "2_2") (pintype "passive"))
    )
    (net (code "26") (name "Net-(D7-+)") (class "Default")
      (node (ref "C3") (pin "1") (pinfunction "1_1") (pintype "passive"))
      (node (ref "D7") (pin "A") (pinfunction "+_A") (pintype "passive"))
      (node (ref "R5") (pin "1") (pinfunction "1_1") (pintype "passive"))
    )
    (net (code "27") (name "Net-(D7--)") (class "Default")
      (node (ref "D7") (pin "C") (pinfunction "-_C") (pintype "passive"))
      (node (ref "D8") (pin "C") (pinfunction "C_C") (pintype "passive"))
    )
    (net (code "28") (name "Net-(D8-PadA)") (class "Default")
      (node (ref "D8") (pin "A") (pinfunction "A_A") (pintype "passive"))
      (node (ref "D9") (pin "C") (pinfunction "C_C") (pintype "passive"))
      (node (ref "R6") (pin "2") (pinfunction "2_2") (pintype "passive"))
    )
    (net (code "29") (name "Net-(D11--)") (class "Default")
      (node (ref "D11") (pin "C") (pinfunction "-_C") (pintype "passive"))
      (node (ref "U$19") (pin "2") (pinfunction "2_2") (pintype "passive"))
    )
    (net (code "30") (name "Net-(D12--)") (class "Default")
      (node (ref "D12") (pin "C") (pinfunction "-_C") (pintype "passive"))
      (node (ref "U$19") (pin "4") (pinfunction "4_4") (pintype "passive"))
    )
    (net (code "31") (name "Net-(D13--)") (class "Default")
      (node (ref "D13") (pin "C") (pinfunction "-_C") (pintype "passive"))
      (node (ref "U$19") (pin "8") (pinfunction "8_8") (pintype "passive"))
    )
    (net (code "32") (name "Net-(D14--)") (class "Default")
      (node (ref "D14") (pin "C") (pinfunction "-_C") (pintype "passive"))
      (node (ref "U$19") (pin "1") (pinfunction "1_1") (pintype "passive"))
    )
    (net (code "33") (name "Net-(D15--)") (class "Default")
      (node (ref "D15") (pin "C") (pinfunction "-_C") (pintype "passive"))
      (node (ref "U$20") (pin "1") (pinfunction "1_1") (pintype "passive"))
    )
    (net (code "34") (name "Net-(D16--)") (class "Default")
      (node (ref "D16") (pin "C") (pinfunction "-_C") (pintype "passive"))
      (node (ref "U$20") (pin "2") (pinfunction "2_2") (pintype "passive"))
    )
    (net (code "35") (name "Net-(D17--)") (class "Default")
      (node (ref "D17") (pin "C") (pinfunction "-_C") (pintype "passive"))
      (node (ref "U$20") (pin "4") (pinfunction "4_4") (pintype "passive"))
    )
    (net (code "36") (name "Net-(D18--)") (class "Default")
      (node (ref "D18") (pin "C") (pinfunction "-_C") (pintype "passive"))
      (node (ref "U$20") (pin "8") (pinfunction "8_8") (pintype "passive"))
    )
    (net (code "37") (name "Net-(D19-PadC)") (class "Default")
      (node (ref "D19") (pin "C") (pinfunction "C_C") (pintype "passive"))
      (node (ref "L3") (pin "1") (pinfunction "1_1") (pintype "passive"))
      (node (ref "R9") (pin "2") (pinfunction "2_2") (pintype "passive"))
    )
    (net (code "38") (name "Net-(D20-+)") (class "Default")
      (node (ref "C5") (pin "1") (pinfunction "1_1") (pintype "passive"))
      (node (ref "D20") (pin "A") (pinfunction "+_A") (pintype "passive"))
      (node (ref "R9") (pin "1") (pinfunction "1_1") (pintype "passive"))
    )
    (net (code "39") (name "Net-(D20--)") (class "Default")
      (node (ref "D20") (pin "C") (pinfunction "-_C") (pintype "passive"))
      (node (ref "D21") (pin "C") (pinfunction "C_C") (pintype "passive"))
    )
    (net (code "40") (name "Net-(D21-PadA)") (class "Default")
      (node (ref "D21") (pin "A") (pinfunction "A_A") (pintype "passive"))
      (node (ref "D22") (pin "C") (pinfunction "C_C") (pintype "passive"))
      (node (ref "R10") (pin "2") (pinfunction "2_2") (pintype "passive"))
    )
    (net (code "41") (name "Net-(D24-PadC)") (class "Default")
      (node (ref "D24") (pin "C") (pinfunction "C_C") (pintype "passive"))
      (node (ref "L4") (pin "1") (pinfunction "1_1") (pintype "passive"))
      (node (ref "R13") (pin "2") (pinfunction "2_2") (pintype "passive"))
    )
    (net (code "42") (name "Net-(D25-+)") (class "Default")
      (node (ref "C7") (pin "1") (pinfunction "1_1") (pintype "passive"))
      (node (ref "D25") (pin "A") (pinfunction "+_A") (pintype "passive"))
      (node (ref "R13") (pin "1") (pinfunction "1_1") (pintype "passive"))
    )
    (net (code "43") (name "Net-(D25--)") (class "Default")
      (node (ref "D25") (pin "C") (pinfunction "-_C") (pintype "passive"))
      (node (ref "D26") (pin "C") (pinfunction "C_C") (pintype "passive"))
    )
    (net (code "44") (name "Net-(D26-PadA)") (class "Default")
      (node (ref "D26") (pin "A") (pinfunction "A_A") (pintype "passive"))
      (node (ref "D27") (pin "C") (pinfunction "C_C") (pintype "passive"))
      (node (ref "R14") (pin "2") (pinfunction "2_2") (pintype "passive"))
    )
    (net (code "45") (name "Net-(D29-PadC)") (class "Default")
      (node (ref "D29") (pin "C") (pinfunction "C_C") (pintype "passive"))
      (node (ref "L5") (pin "1") (pinfunction "1_1") (pintype "passive"))
      (node (ref "R17") (pin "2") (pinfunction "2_2") (pintype "passive"))
    )
    (net (code "46") (name "Net-(D30-+)") (class "Default")
      (node (ref "C9") (pin "1") (pinfunction "1_1") (pintype "passive"))
      (node (ref "D30") (pin "A") (pinfunction "+_A") (pintype "passive"))
      (node (ref "R17") (pin "1") (pinfunction "1_1") (pintype "passive"))
    )
    (net (code "47") (name "Net-(D30--)") (class "Default")
      (node (ref "D30") (pin "C") (pinfunction "-_C") (pintype "passive"))
      (node (ref "D31") (pin "C") (pinfunction "C_C") (pintype "passive"))
    )
    (net (code "48") (name "Net-(D31-PadA)") (class "Default")
      (node (ref "D31") (pin "A") (pinfunction "A_A") (pintype "passive"))
      (node (ref "D32") (pin "C") (pinfunction "C_C") (pintype "passive"))
      (node (ref "R18") (pin "2") (pinfunction "2_2") (pintype "passive"))
    )
    (net (code "49") (name "Net-(D34-PadC)") (class "Default")
      (node (ref "D34") (pin "C") (pinfunction "C_C") (pintype "passive"))
      (node (ref "L6") (pin "1") (pinfunction "1_1") (pintype "passive"))
      (node (ref "R21") (pin "2") (pinfunction "2_2") (pintype "passive"))
    )
    (net (code "50") (name "Net-(D35-+)") (class "Default")
      (node (ref "C11") (pin "1") (pinfunction "1_1") (pintype "passive"))
      (node (ref "D35") (pin "A") (pinfunction "+_A") (pintype "passive"))
      (node (ref "R21") (pin "1") (pinfunction "1_1") (pintype "passive"))
    )
    (net (code "51") (name "Net-(D35--)") (class "Default")
      (node (ref "D35") (pin "C") (pinfunction "-_C") (pintype "passive"))
      (node (ref "D36") (pin "C") (pinfunction "C_C") (pintype "passive"))
    )
    (net (code "52") (name "Net-(D36-PadA)") (class "Default")
      (node (ref "D36") (pin "A") (pinfunction "A_A") (pintype "passive"))
      (node (ref "D37") (pin "C") (pinfunction "C_C") (pintype "passive"))
      (node (ref "R22") (pin "2") (pinfunction "2_2") (pintype "passive"))
    )
    (net (code "53") (name "Net-(D39-PadC)") (class "Default")
      (node (ref "D39") (pin "C") (pinfunction "C_C") (pintype "passive"))
      (node (ref "L7") (pin "1") (pinfunction "1_1") (pintype "passive"))
      (node (ref "R25") (pin "2") (pinfunction "2_2") (pintype "passive"))
    )
    (net (code "54") (name "Net-(D40-+)") (class "Default")
      (node (ref "C13") (pin "1") (pinfunction "1_1") (pintype "passive"))
      (node (ref "D40") (pin "A") (pinfunction "+_A") (pintype "passive"))
      (node (ref "R25") (pin "1") (pinfunction "1_1") (pintype "passive"))
    )
    (net (code "55") (name "Net-(D40--)") (class "Default")
      (node (ref "D40") (pin "C") (pinfunction "-_C") (pintype "passive"))
      (node (ref "D41") (pin "C") (pinfunction "C_C") (pintype "passive"))
    )
    (net (code "56") (name "Net-(D41-PadA)") (class "Default")
      (node (ref "D41") (pin "A") (pinfunction "A_A") (pintype "passive"))
      (node (ref "D42") (pin "C") (pinfunction "C_C") (pintype "passive"))
      (node (ref "R26") (pin "2") (pinfunction "2_2") (pintype "passive"))
    )
    (net (code "57") (name "Net-(D44-PadC)") (class "Default")
      (node (ref "D44") (pin "C") (pinfunction "C_C") (pintype "passive"))
      (node (ref "L8") (pin "1") (pinfunction "1_1") (pintype "passive"))
      (node (ref "R29") (pin "2") (pinfunction "2_2") (pintype "passive"))
    )
    (net (code "58") (name "Net-(D45-+)") (class "Default")
      (node (ref "C15") (pin "1") (pinfunction "1_1") (pintype "passive"))
      (node (ref "D45") (pin "A") (pinfunction "+_A") (pintype "passive"))
      (node (ref "R29") (pin "1") (pinfunction "1_1") (pintype "passive"))
    )
    (net (code "59") (name "Net-(D45--)") (class "Default")
      (node (ref "D45") (pin "C") (pinfunction "-_C") (pintype "passive"))
      (node (ref "D46") (pin "C") (pinfunction "C_C") (pintype "passive"))
    )
    (net (code "60") (name "Net-(D46-PadA)") (class "Default")
      (node (ref "D46") (pin "A") (pinfunction "A_A") (pintype "passive"))
      (node (ref "D47") (pin "C") (pinfunction "C_C") (pintype "passive"))
      (node (ref "R30") (pin "2") (pinfunction "2_2") (pintype "passive"))
    )
    (net (code "61") (name "Net-(IC1A-I)") (class "Default")
      (node (ref "IC1") (pin "13") (pinfunction "I_13") (pintype "input"))
      (node (ref "OK1") (pin "10") (pinfunction "COL_10") (pintype "passive"))
      (node (ref "R33") (pin "2") (pinfunction "2_2") (pintype "passive"))
    )
    (net (code "62") (name "Net-(IC1A-O)") (class "Default")
      (node (ref "IC1") (pin "12") (pinfunction "O_12") (pintype "output"))
      (node (ref "IC3") (pin "2") (pinfunction "1D_2") (pintype "input"))
      (node (ref "R48") (pin "2") (pinfunction "2_2") (pintype "passive"))
    )
    (net (code "63") (name "Net-(IC1B-I)") (class "Default")
      (node (ref "IC1") (pin "11") (pinfunction "I_11") (pintype "input"))
      (node (ref "OK1") (pin "12") (pinfunction "COL_12") (pintype "passive"))
      (node (ref "R34") (pin "2") (pinfunction "2_2") (pintype "passive"))
    )
    (net (code "64") (name "Net-(IC1B-O)") (class "Default")
      (node (ref "IC1") (pin "10") (pinfunction "O_10") (pintype "output"))
      (node (ref "IC3") (pin "3") (pinfunction "2D_3") (pintype "input"))
      (node (ref "R47") (pin "2") (pinfunction "2_2") (pintype "passive"))
    )
    (net (code "65") (name "Net-(IC1C-I)") (class "Default")
      (node (ref "IC1") (pin "9") (pinfunction "I_9") (pintype "input"))
      (node (ref "OK1") (pin "14") (pinfunction "COL_14") (pintype "passive"))
      (node (ref "R35") (pin "2") (pinfunction "2_2") (pintype "passive"))
    )
    (net (code "66") (name "Net-(IC1C-O)") (class "Default")
      (node (ref "IC1") (pin "8") (pinfunction "O_8") (pintype "output"))
      (node (ref "IC3") (pin "4") (pinfunction "3D_4") (pintype "input"))
      (node (ref "R46") (pin "2") (pinfunction "2_2") (pintype "passive"))
    )
    (net (code "67") (name "Net-(IC1D-I)") (class "Default")
      (node (ref "IC1") (pin "1") (pinfunction "I_1") (pintype "input"))
      (node (ref "OK1") (pin "16") (pinfunction "COL_16") (pintype "passive"))
      (node (ref "R36") (pin "2") (pinfunction "2_2") (pintype "passive"))
    )
    (net (code "68") (name "Net-(IC1D-O)") (class "Default")
      (node (ref "IC1") (pin "2") (pinfunction "O_2") (pintype "output"))
      (node (ref "IC3") (pin "5") (pinfunction "4D_5") (pintype "input"))
      (node (ref "R45") (pin "2") (pinfunction "2_2") (pintype "passive"))
    )
    (net (code "69") (name "Net-(IC1E-I)") (class "Default")
      (node (ref "IC1") (pin "3") (pinfunction "I_3") (pintype "input"))
      (node (ref "OK2") (pin "10") (pinfunction "COL_10") (pintype "passive"))
      (node (ref "R37") (pin "2") (pinfunction "2_2") (pintype "passive"))
    )
    (net (code "70") (name "Net-(IC1E-O)") (class "Default")
      (node (ref "IC1") (pin "4") (pinfunction "O_4") (pintype "output"))
      (node (ref "IC3") (pin "6") (pinfunction "5D_6") (pintype "input"))
      (node (ref "R44") (pin "2") (pinfunction "2_2") (pintype "passive"))
    )
    (net (code "71") (name "Net-(IC1F-I)") (class "Default")
      (node (ref "IC1") (pin "5") (pinfunction "I_5") (pintype "input"))
      (node (ref "OK2") (pin "12") (pinfunction "COL_12") (pintype "passive"))
      (node (ref "R38") (pin "2") (pinfunction "2_2") (pintype "passive"))
    )
    (net (code "72") (name "Net-(IC1F-O)") (class "Default")
      (node (ref "IC1") (pin "6") (pinfunction "O_6") (pintype "output"))
      (node (ref "IC3") (pin "7") (pinfunction "6D_7") (pintype "input"))
      (node (ref "R43") (pin "2") (pinfunction "2_2") (pintype "passive"))
    )
    (net (code "73") (name "Net-(IC2A-I)") (class "Default")
      (node (ref "IC2") (pin "13") (pinfunction "I_13") (pintype "input"))
      (node (ref "OK2") (pin "16") (pinfunction "COL_16") (pintype "passive"))
      (node (ref "R40") (pin "2") (pinfunction "2_2") (pintype "passive"))
    )
    (net (code "74") (name "Net-(IC2A-O)") (class "Default")
      (node (ref "IC2") (pin "12") (pinfunction "O_12") (pintype "output"))
      (node (ref "IC3") (pin "9") (pinfunction "8D_9") (pintype "input"))
      (node (ref "R41") (pin "2") (pinfunction "2_2") (pintype "passive"))
    )
    (net (code "75") (name "Net-(IC2B-I)") (class "Default")
      (node (ref "IC2") (pin "11") (pinfunction "I_11") (pintype "input"))
      (node (ref "OK2") (pin "14") (pinfunction "COL_14") (pintype "passive"))
      (node (ref "R39") (pin "2") (pinfunction "2_2") (pintype "passive"))
    )
    (net (code "76") (name "Net-(IC2B-O)") (class "Default")
      (node (ref "IC2") (pin "10") (pinfunction "O_10") (pintype "output"))
      (node (ref "IC3") (pin "8") (pinfunction "7D_8") (pintype "input"))
      (node (ref "R42") (pin "2") (pinfunction "2_2") (pintype "passive"))
    )
    (net (code "77") (name "Net-(JP1-Pad2)") (class "Default")
      (node (ref "JP1") (pin "2") (pinfunction "2_2") (pintype "passive"))
      (node (ref "R50") (pin "1") (pinfunction "1_1") (pintype "passive"))
    )
    (net (code "78") (name "Net-(L1-Pad2)") (class "Default")
      (node (ref "L1") (pin "2") (pinfunction "2_2") (pintype "passive"))
      (node (ref "X1") (pin "1.1") (pinfunction "1_1.1") (pintype "bidirectional"))
      (node (ref "X1") (pin "1.2") (pinfunction "1_1.2") (pintype "bidirectional"))
    )
    (net (code "79") (name "Net-(L2-Pad2)") (class "Default")
      (node (ref "L2") (pin "2") (pinfunction "2_2") (pintype "passive"))
      (node (ref "X1") (pin "2.1") (pinfunction "2_2.1") (pintype "bidirectional"))
      (node (ref "X1") (pin "2.2") (pinfunction "2_2.2") (pintype "bidirectional"))
    )
    (net (code "80") (name "Net-(L3-Pad2)") (class "Default")
      (node (ref "L3") (pin "2") (pinfunction "2_2") (pintype "passive"))
      (node (ref "X2") (pin "1.1") (pinfunction "1_1.1") (pintype "bidirectional"))
      (node (ref "X2") (pin "1.2") (pinfunction "1_1.2") (pintype "bidirectional"))
    )
    (net (code "81") (name "Net-(L4-Pad2)") (class "Default")
      (node (ref "L4") (pin "2") (pinfunction "2_2") (pintype "passive"))
      (node (ref "X2") (pin "2.1") (pinfunction "2_2.1") (pintype "bidirectional"))
      (node (ref "X2") (pin "2.2") (pinfunction "2_2.2") (pintype "bidirectional"))
    )
    (net (code "82") (name "Net-(L5-Pad2)") (class "Default")
      (node (ref "L5") (pin "2") (pinfunction "2_2") (pintype "passive"))
      (node (ref "X3") (pin "1.1") (pinfunction "1_1.1") (pintype "bidirectional"))
      (node (ref "X3") (pin "1.2") (pinfunction "1_1.2") (pintype "bidirectional"))
    )
    (net (code "83") (name "Net-(L6-Pad2)") (class "Default")
      (node (ref "L6") (pin "2") (pinfunction "2_2") (pintype "passive"))
      (node (ref "X3") (pin "2.1") (pinfunction "2_2.1") (pintype "bidirectional"))
      (node (ref "X3") (pin "2.2") (pinfunction "2_2.2") (pintype "bidirectional"))
    )
    (net (code "84") (name "Net-(L7-Pad2)") (class "Default")
      (node (ref "L7") (pin "2") (pinfunction "2_2") (pintype "passive"))
      (node (ref "X4") (pin "1.1") (pinfunction "1_1.1") (pintype "bidirectional"))
      (node (ref "X4") (pin "1.2") (pinfunction "1_1.2") (pintype "bidirectional"))
    )
    (net (code "85") (name "Net-(L8-Pad2)") (class "Default")
      (node (ref "L8") (pin "2") (pinfunction "2_2") (pintype "passive"))
      (node (ref "X4") (pin "2.1") (pinfunction "2_2.1") (pintype "bidirectional"))
      (node (ref "X4") (pin "2.2") (pinfunction "2_2.2") (pintype "bidirectional"))
    )
    (net (code "86") (name "Net-(LED1-PadA)") (class "Default")
      (node (ref "LED1") (pin "A") (pinfunction "A_A") (pintype "passive"))
      (node (ref "R41") (pin "1") (pinfunction "1_1") (pintype "passive"))
    )
    (net (code "87") (name "Net-(LED2-PadA)") (class "Default")
      (node (ref "LED2") (pin "A") (pinfunction "A_A") (pintype "passive"))
      (node (ref "R42") (pin "1") (pinfunction "1_1") (pintype "passive"))
    )
    (net (code "88") (name "Net-(LED3-PadA)") (class "Default")
      (node (ref "LED3") (pin "A") (pinfunction "A_A") (pintype "passive"))
      (node (ref "R43") (pin "1") (pinfunction "1_1") (pintype "passive"))
    )
    (net (code "89") (name "Net-(LED4-PadA)") (class "Default")
      (node (ref "LED4") (pin "A") (pinfunction "A_A") (pintype "passive"))
      (node (ref "R44") (pin "1") (pinfunction "1_1") (pintype "passive"))
    )
    (net (code "90") (name "Net-(LED5-PadA)") (class "Default")
      (node (ref "LED5") (pin "A") (pinfunction "A_A") (pintype "passive"))
      (node (ref "R45") (pin "1") (pinfunction "1_1") (pintype "passive"))
    )
    (net (code "91") (name "Net-(LED6-PadA)") (class "Default")
      (node (ref "LED6") (pin "A") (pinfunction "A_A") (pintype "passive"))
      (node (ref "R46") (pin "1") (pinfunction "1_1") (pintype "passive"))
    )
    (net (code "92") (name "Net-(LED7-PadA)") (class "Default")
      (node (ref "LED7") (pin "A") (pinfunction "A_A") (pintype "passive"))
      (node (ref "R47") (pin "1") (pinfunction "1_1") (pintype "passive"))
    )
    (net (code "93") (name "Net-(LED8-PadA)") (class "Default")
      (node (ref "LED8") (pin "A") (pinfunction "A_A") (pintype "passive"))
      (node (ref "R48") (pin "1") (pinfunction "1_1") (pintype "passive"))
    )
    (net (code "94") (name "Net-(OK1A-A)") (class "Default")
      (node (ref "C8") (pin "1") (pinfunction "1_1") (pintype "passive"))
      (node (ref "OK1") (pin "1") (pinfunction "A_1") (pintype "passive"))
      (node (ref "R15") (pin "1") (pinfunction "1_1") (pintype "passive"))
      (node (ref "R16") (pin "2") (pinfunction "2_2") (pintype "passive"))
      (node (ref "U$4") (pin "2") (pinfunction "C_2") (pintype "passive"))
      (node (ref "U$4") (pin "2.1") (pinfunction "C_2.1") (pintype "passive"))
    )
    (net (code "95") (name "Net-(OK1B-A)") (class "Default")
      (node (ref "C6") (pin "1") (pinfunction "1_1") (pintype "passive"))
      (node (ref "OK1") (pin "3") (pinfunction "A_3") (pintype "passive"))
      (node (ref "R11") (pin "1") (pinfunction "1_1") (pintype "passive"))
      (node (ref "R12") (pin "2") (pinfunction "2_2") (pintype "passive"))
      (node (ref "U$3") (pin "2") (pinfunction "C_2") (pintype "passive"))
      (node (ref "U$3") (pin "2.1") (pinfunction "C_2.1") (pintype "passive"))
    )
    (net (code "96") (name "Net-(OK1C-A)") (class "Default")
      (node (ref "C4") (pin "1") (pinfunction "1_1") (pintype "passive"))
      (node (ref "OK1") (pin "5") (pinfunction "A_5") (pintype "passive"))
      (node (ref "R7") (pin "1") (pinfunction "1_1") (pintype "passive"))
      (node (ref "R8") (pin "2") (pinfunction "2_2") (pintype "passive"))
      (node (ref "U$2") (pin "2") (pinfunction "C_2") (pintype "passive"))
      (node (ref "U$2") (pin "2.1") (pinfunction "C_2.1") (pintype "passive"))
    )
    (net (code "97") (name "Net-(OK1D-A)") (class "Default")
      (node (ref "C2") (pin "1") (pinfunction "1_1") (pintype "passive"))
      (node (ref "OK1") (pin "7") (pinfunction "A_7") (pintype "passive"))
      (node (ref "R3") (pin "1") (pinfunction "1_1") (pintype "passive"))
      (node (ref "R4") (pin "2") (pinfunction "2_2") (pintype "passive"))
      (node (ref "U$1") (pin "2") (pinfunction "C_2") (pintype "passive"))
      (node (ref "U$1") (pin "2.1") (pinfunction "C_2.1") (pintype "passive"))
    )
    (net (code "98") (name "Net-(OK2A-A)") (class "Default")
      (node (ref "C16") (pin "1") (pinfunction "1_1") (pintype "passive"))
      (node (ref "OK2") (pin "1") (pinfunction "A_1") (pintype "passive"))
      (node (ref "R31") (pin "1") (pinfunction "1_1") (pintype "passive"))
      (node (ref "R32") (pin "2") (pinfunction "2_2") (pintype "passive"))
      (node (ref "U$8") (pin "2") (pinfunction "C_2") (pintype "passive"))
      (node (ref "U$8") (pin "2.1") (pinfunction "C_2.1") (pintype "passive"))
    )
    (net (code "99") (name "Net-(OK2B-A)") (class "Default")
      (node (ref "C14") (pin "1") (pinfunction "1_1") (pintype "passive"))
      (node (ref "OK2") (pin "3") (pinfunction "A_3") (pintype "passive"))
      (node (ref "R27") (pin "1") (pinfunction "1_1") (pintype "passive"))
      (node (ref "R28") (pin "2") (pinfunction "2_2") (pintype "passive"))
      (node (ref "U$7") (pin "2") (pinfunction "C_2") (pintype "passive"))
      (node (ref "U$7") (pin "2.1") (pinfunction "C_2.1") (pintype "passive"))
    )
    (net (code "100") (name "Net-(OK2C-A)") (class "Default")
      (node (ref "C12") (pin "1") (pinfunction "1_1") (pintype "passive"))
      (node (ref "OK2") (pin "5") (pinfunction "A_5") (pintype "passive"))
      (node (ref "R23") (pin "1") (pinfunction "1_1") (pintype "passive"))
      (node (ref "R24") (pin "2") (pinfunction "2_2") (pintype "passive"))
      (node (ref "U$6") (pin "2") (pinfunction "C_2") (pintype "passive"))
      (node (ref "U$6") (pin "2.1") (pinfunction "C_2.1") (pintype "passive"))
    )
    (net (code "101") (name "Net-(OK2D-A)") (class "Default")
      (node (ref "C10") (pin "1") (pinfunction "1_1") (pintype "passive"))
      (node (ref "OK2") (pin "7") (pinfunction "A_7") (pintype "passive"))
      (node (ref "R19") (pin "1") (pinfunction "1_1") (pintype "passive"))
      (node (ref "R20") (pin "2") (pinfunction "2_2") (pintype "passive"))
      (node (ref "U$5") (pin "2") (pinfunction "C_2") (pintype "passive"))
      (node (ref "U$5") (pin "2.1") (pinfunction "C_2.1") (pintype "passive"))
    )
    (net (code "102") (name "Net-(Q2-OUT)") (class "Default")
      (node (ref "Q2") (pin "3") (pinfunction "OUT_3") (pintype "output"))
      (node (ref "U1") (pin "7") (pinfunction "PB6(XTAL1/TOSC1)_7") (pintype "bidirectional"))
    )
    (net (code "103") (name "Net-(U$1-B)") (class "Default")
      (node (ref "D4") (pin "A") (pinfunction "A_A") (pintype "passive"))
      (node (ref "R3") (pin "2") (pinfunction "2_2") (pintype "passive"))
      (node (ref "U$1") (pin "1") (pinfunction "B_1") (pintype "passive"))
    )
    (net (code "104") (name "Net-(U$1-E)") (class "Default")
      (node (ref "R2") (pin "1") (pinfunction "1_1") (pintype "passive"))
      (node (ref "U$1") (pin "3") (pinfunction "E_3") (pintype "passive"))
    )
    (net (code "105") (name "Net-(U$2-B)") (class "Default")
      (node (ref "D9") (pin "A") (pinfunction "A_A") (pintype "passive"))
      (node (ref "R7") (pin "2") (pinfunction "2_2") (pintype "passive"))
      (node (ref "U$2") (pin "1") (pinfunction "B_1") (pintype "passive"))
    )
    (net (code "106") (name "Net-(U$2-E)") (class "Default")
      (node (ref "R6") (pin "1") (pinfunction "1_1") (pintype "passive"))
      (node (ref "U$2") (pin "3") (pinfunction "E_3") (pintype "passive"))
    )
    (net (code "107") (name "Net-(U$3-B)") (class "Default")
      (node (ref "D22") (pin "A") (pinfunction "A_A") (pintype "passive"))
      (node (ref "R11") (pin "2") (pinfunction "2_2") (pintype "passive"))
      (node (ref "U$3") (pin "1") (pinfunction "B_1") (pintype "passive"))
    )
    (net (code "108") (name "Net-(U$3-E)") (class "Default")
      (node (ref "R10") (pin "1") (pinfunction "1_1") (pintype "passive"))
      (node (ref "U$3") (pin "3") (pinfunction "E_3") (pintype "passive"))
    )
    (net (code "109") (name "Net-(U$4-B)") (class "Default")
      (node (ref "D27") (pin "A") (pinfunction "A_A") (pintype "passive"))
      (node (ref "R15") (pin "2") (pinfunction "2_2") (pintype "passive"))
      (node (ref "U$4") (pin "1") (pinfunction "B_1") (pintype "passive"))
    )
    (net (code "110") (name "Net-(U$4-E)") (class "Default")
      (node (ref "R14") (pin "1") (pinfunction "1_1") (pintype "passive"))
      (node (ref "U$4") (pin "3") (pinfunction "E_3") (pintype "passive"))
    )
    (net (code "111") (name "Net-(U$5-B)") (class "Default")
      (node (ref "D32") (pin "A") (pinfunction "A_A") (pintype "passive"))
      (node (ref "R19") (pin "2") (pinfunction "2_2") (pintype "passive"))
      (node (ref "U$5") (pin "1") (pinfunction "B_1") (pintype "passive"))
    )
    (net (code "112") (name "Net-(U$5-E)") (class "Default")
      (node (ref "R18") (pin "1") (pinfunction "1_1") (pintype "passive"))
      (node (ref "U$5") (pin "3") (pinfunction "E_3") (pintype "passive"))
    )
    (net (code "113") (name "Net-(U$6-B)") (class "Default")
      (node (ref "D37") (pin "A") (pinfunction "A_A") (pintype "passive"))
      (node (ref "R23") (pin "2") (pinfunction "2_2") (pintype "passive"))
      (node (ref "U$6") (pin "1") (pinfunction "B_1") (pintype "passive"))
    )
    (net (code "114") (name "Net-(U$6-E)") (class "Default")
      (node (ref "R22") (pin "1") (pinfunction "1_1") (pintype "passive"))
      (node (ref "U$6") (pin "3") (pinfunction "E_3") (pintype "passive"))
    )
    (net (code "115") (name "Net-(U$7-B)") (class "Default")
      (node (ref "D42") (pin "A") (pinfunction "A_A") (pintype "passive"))
      (node (ref "R27") (pin "2") (pinfunction "2_2") (pintype "passive"))
      (node (ref "U$7") (pin "1") (pinfunction "B_1") (pintype "passive"))
    )
    (net (code "116") (name "Net-(U$7-E)") (class "Default")
      (node (ref "R26") (pin "1") (pinfunction "1_1") (pintype "passive"))
      (node (ref "U$7") (pin "3") (pinfunction "E_3") (pintype "passive"))
    )
    (net (code "117") (name "Net-(U$8-B)") (class "Default")
      (node (ref "D47") (pin "A") (pinfunction "A_A") (pintype "passive"))
      (node (ref "R31") (pin "2") (pinfunction "2_2") (pintype "passive"))
      (node (ref "U$8") (pin "1") (pinfunction "B_1") (pintype "passive"))
    )
    (net (code "118") (name "Net-(U$8-E)") (class "Default")
      (node (ref "R30") (pin "1") (pinfunction "1_1") (pintype "passive"))
      (node (ref "U$8") (pin "3") (pinfunction "E_3") (pintype "passive"))
    )
    (net (code "119") (name "RESET") (class "Default")
      (node (ref "J1") (pin "5") (pinfunction "5_5") (pintype "bidirectional"))
      (node (ref "R49") (pin "1") (pinfunction "1_1") (pintype "passive"))
      (node (ref "U1") (pin "29") (pinfunction "PC6(/RESET)_29") (pintype "bidirectional"))
    )
    (net (code "120") (name "RXD") (class "Default")
      (node (ref "IC5") (pin "1") (pinfunction "RO_1") (pintype "output"))
      (node (ref "U1") (pin "30") (pinfunction "PD0(RXD)_30") (pintype "bidirectional"))
    )
    (net (code "121") (name "SCK") (class "Default")
      (node (ref "J1") (pin "3") (pinfunction "3_3") (pintype "bidirectional"))
      (node (ref "U1") (pin "17") (pinfunction "PB5(SCK)_17") (pintype "bidirectional"))
    )
    (net (code "122") (name "TXD") (class "Default")
      (node (ref "IC5") (pin "4") (pinfunction "DI_4") (pintype "input"))
      (node (ref "U1") (pin "31") (pinfunction "PD1(TXD)_31") (pintype "bidirectional"))
    )
    (net (code "123") (name "unconnected-(IC2C-O-Pad8)") (class "Default")
      (node (ref "IC2") (pin "8") (pinfunction "O_8") (pintype "output"))
    )
    (net (code "124") (name "unconnected-(IC2D-O-Pad2)") (class "Default")
      (node (ref "IC2") (pin "2") (pinfunction "O_2") (pintype "output"))
    )
    (net (code "125") (name "unconnected-(IC2E-O-Pad4)") (class "Default")
      (node (ref "IC2") (pin "4") (pinfunction "O_4") (pintype "output"))
    )
    (net (code "126") (name "unconnected-(IC2F-O-Pad6)") (class "Default")
      (node (ref "IC2") (pin "6") (pinfunction "O_6") (pintype "output"))
    )
    (net (code "127") (name "unconnected-(Q2-TS-Pad1)") (class "Default")
      (node (ref "Q2") (pin "1") (pinfunction "TS_1") (pintype "passive"))
    )
    (net (code "128") (name "unconnected-(U1-PB0(ICP)-Pad12)") (class "Default")
      (node (ref "U1") (pin "12") (pinfunction "PB0(ICP)_12") (pintype "bidirectional"))
    )
    (net (code "129") (name "unconnected-(U1-PB1(OC1A)-Pad13)") (class "Default")
      (node (ref "U1") (pin "13") (pinfunction "PB1(OC1A)_13") (pintype "bidirectional"))
    )
    (net (code "130") (name "unconnected-(U1-PB2(SS{slash}OC1B)-Pad14)") (class "Default")
      (node (ref "U1") (pin "14") (pinfunction "PB2(SS/OC1B)_14") (pintype "bidirectional"))
    )
    (net (code "131") (name "unconnected-(U1-PB7(XTAL2{slash}TOSC2)-Pad8)") (class "Default")
      (node (ref "U1") (pin "8") (pinfunction "PB7(XTAL2/TOSC2)_8") (pintype "bidirectional"))
    )
    (net (code "132") (name "unconnected-(U1-PD5(T1)-Pad9)") (class "Default")
      (node (ref "U1") (pin "9") (pinfunction "PD5(T1)_9") (pintype "bidirectional"))
    )
    (net (code "133") (name "unconnected-(U1-PD6(AIN0)-Pad10)") (class "Default")
      (node (ref "U1") (pin "10") (pinfunction "PD6(AIN0)_10") (pintype "bidirectional"))
    )
  )
)
